# Sheet3.net
KiCad netlist of a schematic drawn in Altium Designer
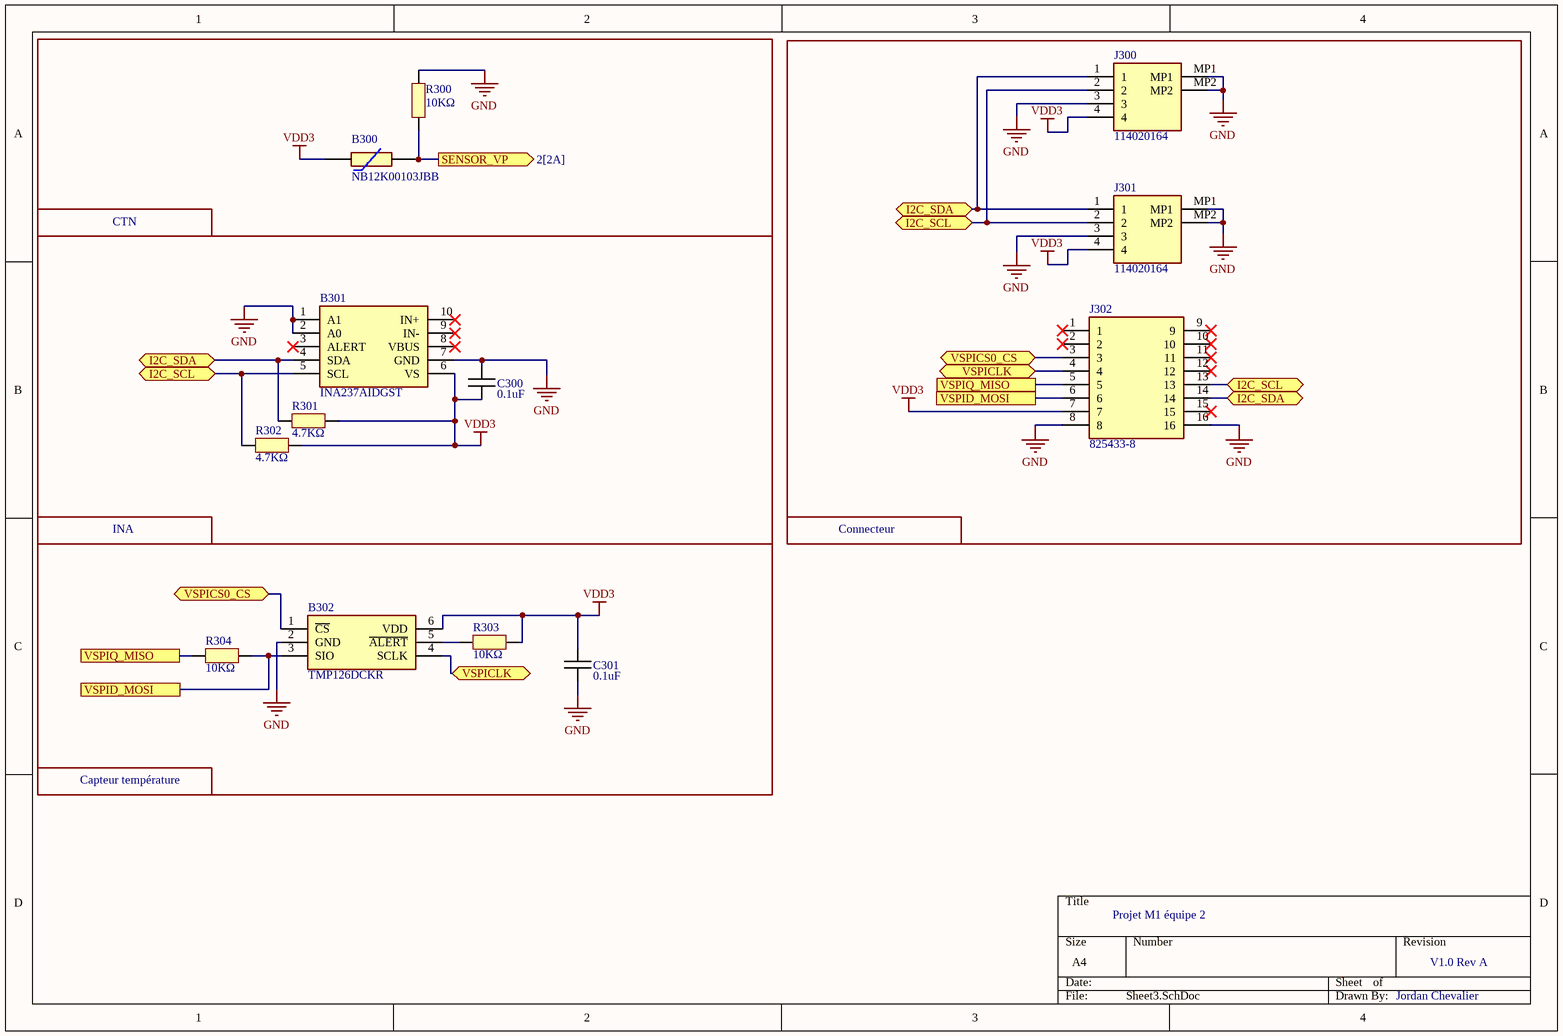
[diagram p0: Sheet3.SchDoc]

(export (version "E")
  (design (tool "Eeschema 10.0.6"))
  (components
    (comp (ref "B300")
      (value "NB12K00103JBB")
      (footprint "RESC2212X50N")
      (description "NTC SMD Thermistor, NB12K, 10K, 5% AVX 10k 0805 Protection NTC Thermistor, 5s, 2 x 1.25 x 1.3mm")
      (fields (field (name "MOUSER PART NUMBER") "581-NB12K00103JBB"))
      (libsource (lib "SCHLibrary") (part "NB12K00103JBB"))
    )
    (comp (ref "B301")
      (value "INA237AIDGST")
      (footprint "SOP50P490X110-10N")
      (fields (field (name "MOUSER PART NUMBER") "595-INA237AIDGST"))
      (libsource (lib "SCHLibrary") (part "INA237AIDGST"))
    )
    (comp (ref "B302")
      (value "TMP126DCKR")
      (footprint "SOT65P210X110-6N")
      (fields (field (name "MOUSER PART NUMBER") "595-TMP126DCKR"))
      (libsource (lib "SCHLibrary") (part "TMP126DCKR"))
    )
    (comp (ref "C300")
      (value "0.1uF")
      (footprint "CAPC1005X06N")
      (libsource (lib "SCHLibrary") (part "Capacitor"))
    )
    (comp (ref "C301")
      (value "0.1uF")
      (footprint "CAPC1005X06N")
      (libsource (lib "SCHLibrary") (part "Capacitor"))
    )
    (comp (ref "J300")
      (value "114020164")
      (footprint "114020164")
      (description "Seeed Studio Accessories Grove Female Header - SMD-4P-2.0mm-90D-20Pcs")
      (fields (field (name "MOUSER PART NUMBER") "713-114020164"))
      (libsource (lib "SCHLibrary") (part "114020164"))
    )
    (comp (ref "J301")
      (value "114020164")
      (footprint "114020164")
      (description "Seeed Studio Accessories Grove Female Header - SMD-4P-2.0mm-90D-20Pcs")
      (fields (field (name "MOUSER PART NUMBER") "713-114020164"))
      (libsource (lib "SCHLibrary") (part "114020164"))
    )
    (comp (ref "J302")
      (value "825433-8")
      (footprint "Connect-Mikronus")
      (description "Headers & Wire Housings 8P double for connection mikrobus")
      (fields (field (name "MOUSER PART NUMBER") "571-825433-8"))
      (libsource (lib "SCHLibrary") (part "Connect-Mikrobus"))
    )
    (comp (ref "R300") (value "10KΩ") (footprint "RESC1005X06N") (libsource (lib "") (part "Resistor_1")))
    (comp (ref "R301")
      (value "4.7KΩ")
      (footprint "RESC1005X06N")
      (libsource (lib "SCHLibrary") (part "Resistor"))
    )
    (comp (ref "R302")
      (value "4.7KΩ")
      (footprint "RESC1005X06N")
      (libsource (lib "SCHLibrary") (part "Resistor"))
    )
    (comp (ref "R303")
      (value "10KΩ")
      (footprint "RESC1005X06N")
      (libsource (lib "SCHLibrary") (part "Resistor"))
    )
    (comp (ref "R304")
      (value "10KΩ")
      (footprint "RESC1005X06N")
      (libsource (lib "SCHLibrary") (part "Resistor"))
    )
  )
  (nets
    (net (code "1") (name "/I2C_SCL") (class "Default")
      (node (ref "B301") (pin "5") (pinfunction "SCL_5") (pintype "passive"))
      (node (ref "J300") (pin "2") (pinfunction "2_2") (pintype "passive"))
      (node (ref "J301") (pin "2") (pinfunction "2_2") (pintype "passive"))
      (node (ref "J302") (pin "13") (pinfunction "13_13") (pintype "passive"))
      (node (ref "R302") (pin "1") (pinfunction "1_1") (pintype "passive"))
    )
    (net (code "2") (name "/I2C_SDA") (class "Default")
      (node (ref "B301") (pin "4") (pinfunction "SDA_4") (pintype "passive"))
      (node (ref "J300") (pin "1") (pinfunction "1_1") (pintype "passive"))
      (node (ref "J301") (pin "1") (pinfunction "1_1") (pintype "passive"))
      (node (ref "J302") (pin "14") (pinfunction "14_14") (pintype "passive"))
      (node (ref "R301") (pin "1") (pinfunction "1_1") (pintype "passive"))
    )
    (net (code "3") (name "/SENSOR_VP") (class "Default")
      (node (ref "B300") (pin "2") (pinfunction "2_2") (pintype "passive"))
      (node (ref "R300") (pin "1") (pinfunction "1_1") (pintype "passive"))
    )
    (net (code "4") (name "/VSPICLK") (class "Default")
      (node (ref "B302") (pin "4") (pinfunction "SCLK_4") (pintype "passive"))
      (node (ref "J302") (pin "4") (pinfunction "4_4") (pintype "passive"))
    )
    (net (code "5") (name "/VSPICS0_CS") (class "Default")
      (node (ref "B302") (pin "1") (pinfunction "~{CS}_1") (pintype "passive"))
      (node (ref "J302") (pin "3") (pinfunction "3_3") (pintype "passive"))
    )
    (net (code "6") (name "/VSPID_MOSI") (class "Default")
      (node (ref "B302") (pin "3") (pinfunction "SIO_3") (pintype "passive"))
      (node (ref "J302") (pin "6") (pinfunction "6_6") (pintype "passive"))
      (node (ref "R304") (pin "2") (pinfunction "2_2") (pintype "passive"))
    )
    (net (code "7") (name "/VSPIQ_MISO") (class "Default")
      (node (ref "J302") (pin "5") (pinfunction "5_5") (pintype "passive"))
      (node (ref "R304") (pin "1") (pinfunction "1_1") (pintype "passive"))
    )
    (net (code "8") (name "GND") (class "Default")
      (node (ref "B301") (pin "1") (pinfunction "A1_1") (pintype "passive"))
      (node (ref "B301") (pin "2") (pinfunction "A0_2") (pintype "passive"))
      (node (ref "B301") (pin "7") (pinfunction "GND_7") (pintype "passive"))
      (node (ref "B302") (pin "2") (pinfunction "GND_2") (pintype "passive"))
      (node (ref "C300") (pin "1") (pinfunction "1_1") (pintype "passive"))
      (node (ref "C301") (pin "2") (pinfunction "2_2") (pintype "passive"))
      (node (ref "J300") (pin "3") (pinfunction "3_3") (pintype "passive"))
      (node (ref "J300") (pin "MP1") (pinfunction "MP1_MP1") (pintype "passive"))
      (node (ref "J300") (pin "MP2") (pinfunction "MP2_MP2") (pintype "passive"))
      (node (ref "J301") (pin "3") (pinfunction "3_3") (pintype "passive"))
      (node (ref "J301") (pin "MP1") (pinfunction "MP1_MP1") (pintype "passive"))
      (node (ref "J301") (pin "MP2") (pinfunction "MP2_MP2") (pintype "passive"))
      (node (ref "J302") (pin "16") (pinfunction "16_16") (pintype "passive"))
      (node (ref "J302") (pin "8") (pinfunction "8_8") (pintype "passive"))
      (node (ref "R300") (pin "2") (pinfunction "2_2") (pintype "passive"))
    )
    (net (code "9") (name "Net-(B302-~{ALERT})") (class "Default")
      (node (ref "B302") (pin "5") (pinfunction "~{ALERT}_5") (pintype "passive"))
      (node (ref "R303") (pin "1") (pinfunction "1_1") (pintype "passive"))
    )
    (net (code "10") (name "VDD3") (class "Default")
      (node (ref "B300") (pin "1") (pinfunction "1_1") (pintype "passive"))
      (node (ref "B301") (pin "6") (pinfunction "VS_6") (pintype "passive"))
      (node (ref "B302") (pin "6") (pinfunction "VDD_6") (pintype "passive"))
      (node (ref "C300") (pin "2") (pinfunction "2_2") (pintype "passive"))
      (node (ref "C301") (pin "1") (pinfunction "1_1") (pintype "passive"))
      (node (ref "J300") (pin "4") (pinfunction "4_4") (pintype "passive"))
      (node (ref "J301") (pin "4") (pinfunction "4_4") (pintype "passive"))
      (node (ref "J302") (pin "7") (pinfunction "7_7") (pintype "passive"))
      (node (ref "R301") (pin "2") (pinfunction "2_2") (pintype "passive"))
      (node (ref "R302") (pin "2") (pinfunction "2_2") (pintype "passive"))
      (node (ref "R303") (pin "2") (pinfunction "2_2") (pintype "passive"))
    )
    (net (code "11") (name "unconnected-(B301-ALERT-Pad3)") (class "Default")
      (node (ref "B301") (pin "3") (pinfunction "ALERT_3") (pintype "passive+no_connect"))
    )
    (net (code "12") (name "unconnected-(B301-IN+-Pad10)") (class "Default")
      (node (ref "B301") (pin "10") (pinfunction "IN+_10") (pintype "passive+no_connect"))
    )
    (net (code "13") (name "unconnected-(B301-IN--Pad9)") (class "Default")
      (node (ref "B301") (pin "9") (pinfunction "IN-_9") (pintype "passive+no_connect"))
    )
    (net (code "14") (name "unconnected-(B301-VBUS-Pad8)") (class "Default")
      (node (ref "B301") (pin "8") (pinfunction "VBUS_8") (pintype "passive+no_connect"))
    )
    (net (code "15") (name "unconnected-(J302-Pad1)") (class "Default")
      (node (ref "J302") (pin "1") (pinfunction "1_1") (pintype "passive+no_connect"))
    )
    (net (code "16") (name "unconnected-(J302-Pad2)") (class "Default")
      (node (ref "J302") (pin "2") (pinfunction "2_2") (pintype "passive+no_connect"))
    )
    (net (code "17") (name "unconnected-(J302-Pad9)") (class "Default")
      (node (ref "J302") (pin "9") (pinfunction "9_9") (pintype "passive+no_connect"))
    )
    (net (code "18") (name "unconnected-(J302-Pad10)") (class "Default")
      (node (ref "J302") (pin "10") (pinfunction "10_10") (pintype "passive+no_connect"))
    )
    (net (code "19") (name "unconnected-(J302-Pad11)") (class "Default")
      (node (ref "J302") (pin "11") (pinfunction "11_11") (pintype "passive+no_connect"))
    )
    (net (code "20") (name "unconnected-(J302-Pad12)") (class "Default")
      (node (ref "J302") (pin "12") (pinfunction "12_12") (pintype "passive+no_connect"))
    )
    (net (code "21") (name "unconnected-(J302-Pad15)") (class "Default")
      (node (ref "J302") (pin "15") (pinfunction "15_15") (pintype "passive+no_connect"))
    )
  )
)
